# FingersFlexpcb.net
KiCad netlist of a schematic drawn in EAGLE
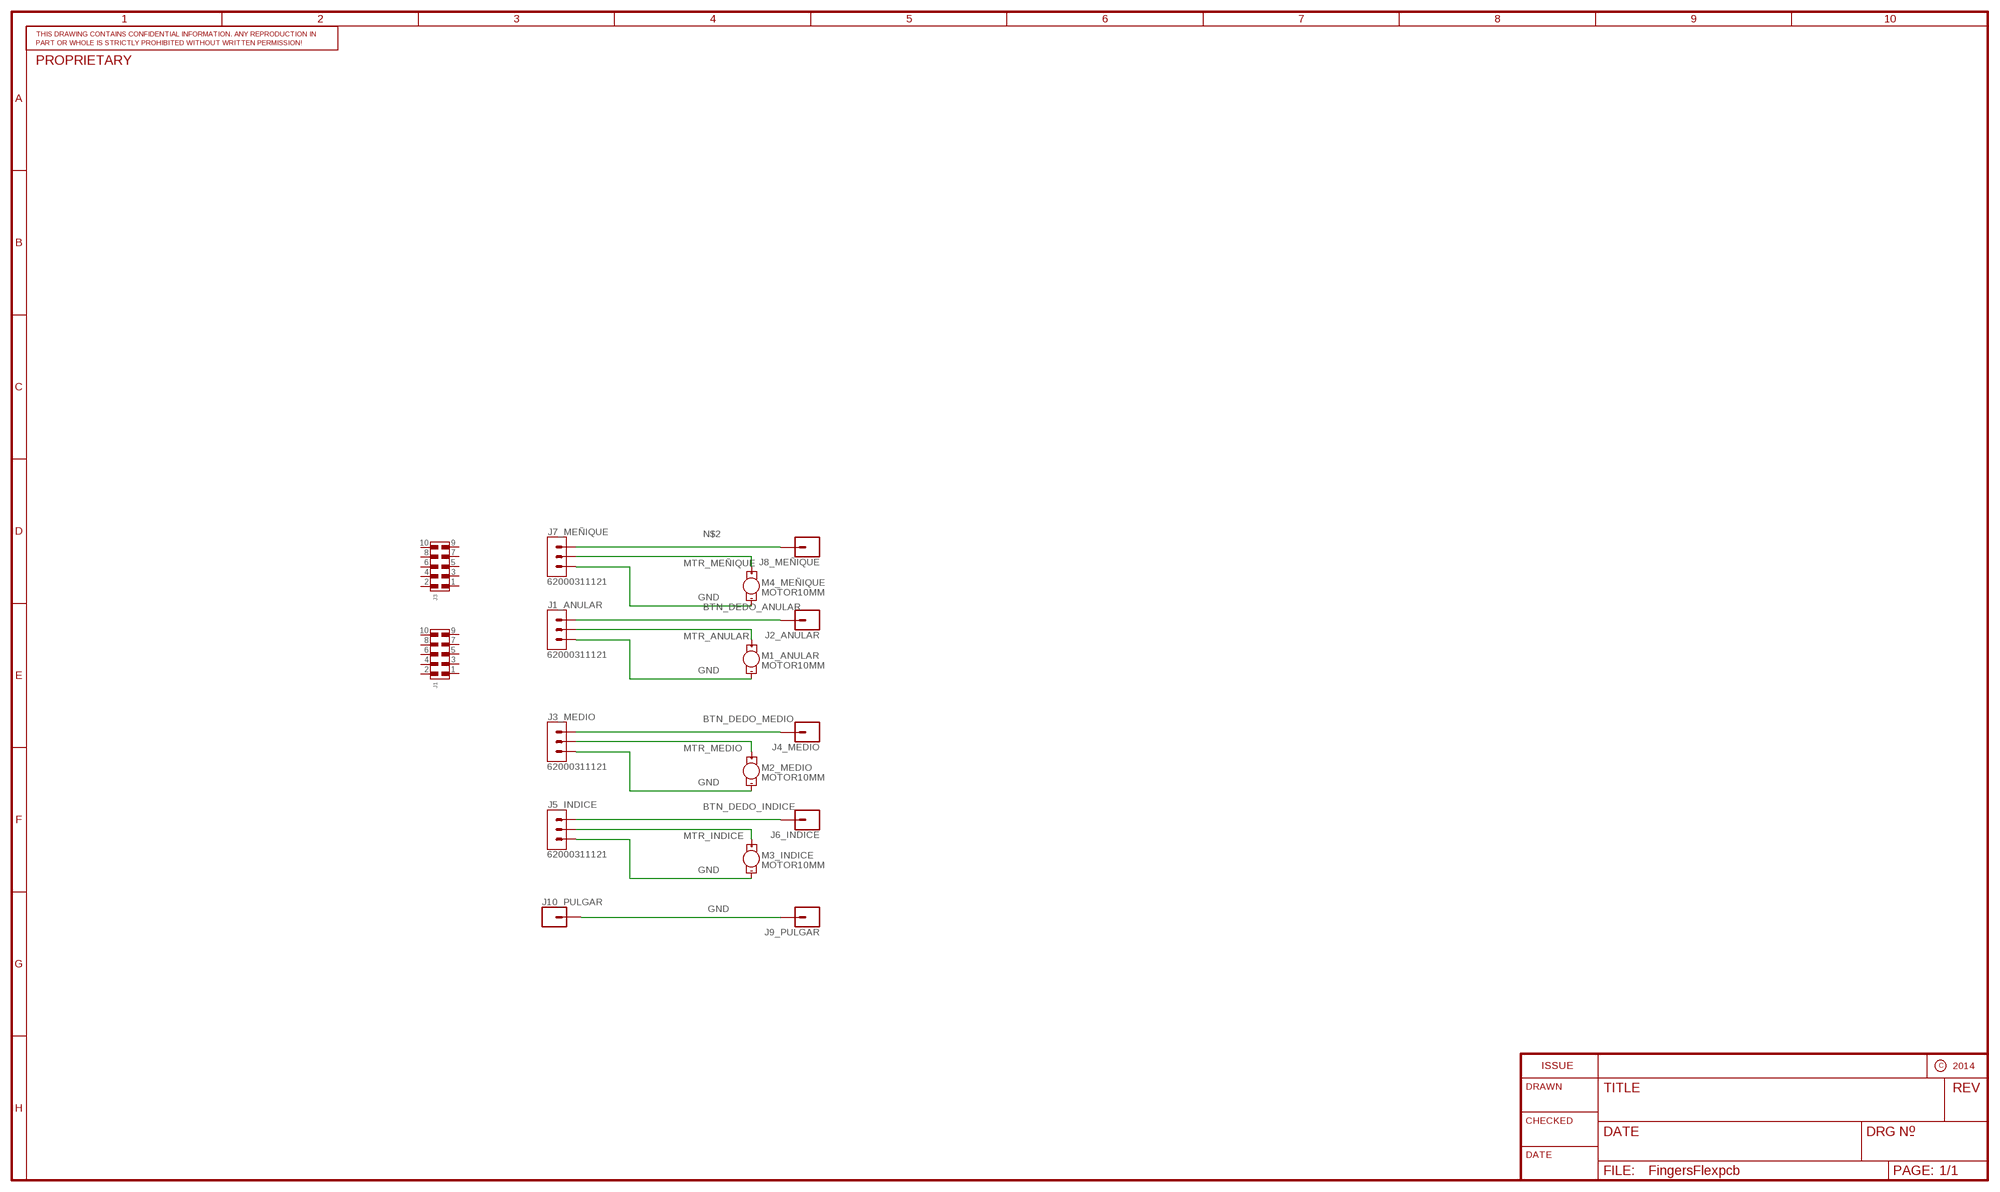
[diagram p0: schematic, sheet 1]

(export (version "E")
  (design (tool "Eeschema 10.0.6"))
  (components
    (comp (ref "J1")
      (value "6100XX21121_61001021121")
      (footprint "eagle-import:61001021121")
      (libsource (lib "eagle-import") (part "6100XX21121_61001021121"))
    )
    (comp (ref "J1_ANULAR")
      (value "62000311121")
      (footprint "eagle-import:62000311121")
      (fields (field (name "MANUFACTURER") " Würth Elektronik ") (field (name "CREATED_BY") "PCBLayout.com"))
      (libsource (lib "eagle-import") (part "62000311121"))
    )
    (comp (ref "J2_ANULAR")
      (value "CONN_01")
      (footprint "eagle-import:1X01")
      (libsource (lib "eagle-import") (part "CONN_01"))
    )
    (comp (ref "J3")
      (value "6100XX21121_61001021121")
      (footprint "eagle-import:61001021121")
      (libsource (lib "eagle-import") (part "6100XX21121_61001021121"))
    )
    (comp (ref "J3_MEDIO")
      (value "62000311121")
      (footprint "eagle-import:62000311121")
      (fields (field (name "MANUFACTURER") " Würth Elektronik ") (field (name "CREATED_BY") "PCBLayout.com"))
      (libsource (lib "eagle-import") (part "62000311121"))
    )
    (comp (ref "J4_MEDIO")
      (value "CONN_01")
      (footprint "eagle-import:1X01")
      (libsource (lib "eagle-import") (part "CONN_01"))
    )
    (comp (ref "J5_INDICE")
      (value "62000311121")
      (footprint "eagle-import:62000311121")
      (fields (field (name "MANUFACTURER") " Würth Elektronik ") (field (name "CREATED_BY") "PCBLayout.com"))
      (libsource (lib "eagle-import") (part "62000311121"))
    )
    (comp (ref "J6_INDICE")
      (value "CONN_01")
      (footprint "eagle-import:1X01")
      (libsource (lib "eagle-import") (part "CONN_01"))
    )
    (comp (ref "J7_MEÑIQUE")
      (value "62000311121")
      (footprint "eagle-import:62000311121")
      (fields (field (name "MANUFACTURER") " Würth Elektronik ") (field (name "CREATED_BY") "PCBLayout.com"))
      (libsource (lib "eagle-import") (part "62000311121"))
    )
    (comp (ref "J8_MEÑIQUE")
      (value "CONN_01")
      (footprint "eagle-import:1X01")
      (libsource (lib "eagle-import") (part "CONN_01"))
    )
    (comp (ref "J9_PULGAR")
      (value "CONN_01")
      (footprint "eagle-import:1X01")
      (libsource (lib "eagle-import") (part "CONN_01"))
    )
    (comp (ref "J10_PULGAR")
      (value "CONN_01")
      (footprint "eagle-import:1X01")
      (libsource (lib "eagle-import") (part "CONN_01"))
    )
    (comp (ref "M1_ANULAR")
      (value "MOTOR10MM")
      (footprint "eagle-import:VIBE-MOTOR-10MM")
      (libsource (lib "eagle-import") (part "MOTOR10MM"))
    )
    (comp (ref "M2_MEDIO")
      (value "MOTOR10MM")
      (footprint "eagle-import:VIBE-MOTOR-10MM")
      (libsource (lib "eagle-import") (part "MOTOR10MM"))
    )
    (comp (ref "M3_INDICE")
      (value "MOTOR10MM")
      (footprint "eagle-import:VIBE-MOTOR-10MM")
      (libsource (lib "eagle-import") (part "MOTOR10MM"))
    )
    (comp (ref "M4_MEÑIQUE")
      (value "MOTOR10MM")
      (footprint "eagle-import:VIBE-MOTOR-10MM")
      (libsource (lib "eagle-import") (part "MOTOR10MM"))
    )
  )
  (nets
    (net (code "1") (name "/BTN_DEDO_ANULAR") (class "Default")
      (node (ref "J1_ANULAR") (pin "1") (pinfunction "1_1") (pintype "passive"))
      (node (ref "J2_ANULAR") (pin "1") (pinfunction "1_1") (pintype "passive"))
    )
    (net (code "2") (name "/BTN_DEDO_INDICE") (class "Default")
      (node (ref "J5_INDICE") (pin "1") (pinfunction "1_1") (pintype "passive"))
      (node (ref "J6_INDICE") (pin "1") (pinfunction "1_1") (pintype "passive"))
    )
    (net (code "3") (name "/BTN_DEDO_MEDIO") (class "Default")
      (node (ref "J3_MEDIO") (pin "1") (pinfunction "1_1") (pintype "passive"))
      (node (ref "J4_MEDIO") (pin "1") (pinfunction "1_1") (pintype "passive"))
    )
    (net (code "4") (name "/GND") (class "Default")
      (node (ref "J10_PULGAR") (pin "1") (pinfunction "1_1") (pintype "passive"))
      (node (ref "J1_ANULAR") (pin "3") (pinfunction "3_3") (pintype "passive"))
      (node (ref "J3_MEDIO") (pin "3") (pinfunction "3_3") (pintype "passive"))
      (node (ref "J5_INDICE") (pin "3") (pinfunction "3_3") (pintype "passive"))
      (node (ref "J7_MEÑIQUE") (pin "3") (pinfunction "3_3") (pintype "passive"))
      (node (ref "J9_PULGAR") (pin "1") (pinfunction "1_1") (pintype "passive"))
      (node (ref "M1_ANULAR") (pin "-") (pinfunction "-_-") (pintype "bidirectional"))
      (node (ref "M2_MEDIO") (pin "-") (pinfunction "-_-") (pintype "bidirectional"))
      (node (ref "M3_INDICE") (pin "-") (pinfunction "-_-") (pintype "bidirectional"))
      (node (ref "M4_MEÑIQUE") (pin "-") (pinfunction "-_-") (pintype "bidirectional"))
    )
    (net (code "5") (name "/MTR_ANULAR") (class "Default")
      (node (ref "J1_ANULAR") (pin "2") (pinfunction "2_2") (pintype "passive"))
      (node (ref "M1_ANULAR") (pin "+") (pinfunction "+_+") (pintype "bidirectional"))
    )
    (net (code "6") (name "/MTR_INDICE") (class "Default")
      (node (ref "J5_INDICE") (pin "2") (pinfunction "2_2") (pintype "passive"))
      (node (ref "M3_INDICE") (pin "+") (pinfunction "+_+") (pintype "bidirectional"))
    )
    (net (code "7") (name "/MTR_MEDIO") (class "Default")
      (node (ref "J3_MEDIO") (pin "2") (pinfunction "2_2") (pintype "passive"))
      (node (ref "M2_MEDIO") (pin "+") (pinfunction "+_+") (pintype "bidirectional"))
    )
    (net (code "8") (name "/MTR_MEÑIQUE") (class "Default")
      (node (ref "J7_MEÑIQUE") (pin "2") (pinfunction "2_2") (pintype "passive"))
      (node (ref "M4_MEÑIQUE") (pin "+") (pinfunction "+_+") (pintype "bidirectional"))
    )
    (net (code "9") (name "/N$2") (class "Default")
      (node (ref "J7_MEÑIQUE") (pin "1") (pinfunction "1_1") (pintype "passive"))
      (node (ref "J8_MEÑIQUE") (pin "1") (pinfunction "1_1") (pintype "passive"))
    )
    (net (code "10") (name "unconnected-(J1-Pad1)") (class "Default")
      (node (ref "J1") (pin "1") (pinfunction "1_1") (pintype "passive"))
    )
    (net (code "11") (name "unconnected-(J1-Pad2)") (class "Default")
      (node (ref "J1") (pin "2") (pinfunction "2_2") (pintype "passive"))
    )
    (net (code "12") (name "unconnected-(J1-Pad3)") (class "Default")
      (node (ref "J1") (pin "3") (pinfunction "3_3") (pintype "passive"))
    )
    (net (code "13") (name "unconnected-(J1-Pad4)") (class "Default")
      (node (ref "J1") (pin "4") (pinfunction "4_4") (pintype "passive"))
    )
    (net (code "14") (name "unconnected-(J1-Pad5)") (class "Default")
      (node (ref "J1") (pin "5") (pinfunction "5_5") (pintype "passive"))
    )
    (net (code "15") (name "unconnected-(J1-Pad6)") (class "Default")
      (node (ref "J1") (pin "6") (pinfunction "6_6") (pintype "passive"))
    )
    (net (code "16") (name "unconnected-(J1-Pad7)") (class "Default")
      (node (ref "J1") (pin "7") (pinfunction "7_7") (pintype "passive"))
    )
    (net (code "17") (name "unconnected-(J1-Pad8)") (class "Default")
      (node (ref "J1") (pin "8") (pinfunction "8_8") (pintype "passive"))
    )
    (net (code "18") (name "unconnected-(J1-Pad9)") (class "Default")
      (node (ref "J1") (pin "9") (pinfunction "9_9") (pintype "passive"))
    )
    (net (code "19") (name "unconnected-(J1-Pad10)") (class "Default")
      (node (ref "J1") (pin "10") (pinfunction "10_10") (pintype "passive"))
    )
    (net (code "20") (name "unconnected-(J3-Pad1)") (class "Default")
      (node (ref "J3") (pin "1") (pinfunction "1_1") (pintype "passive"))
    )
    (net (code "21") (name "unconnected-(J3-Pad2)") (class "Default")
      (node (ref "J3") (pin "2") (pinfunction "2_2") (pintype "passive"))
    )
    (net (code "22") (name "unconnected-(J3-Pad3)") (class "Default")
      (node (ref "J3") (pin "3") (pinfunction "3_3") (pintype "passive"))
    )
    (net (code "23") (name "unconnected-(J3-Pad4)") (class "Default")
      (node (ref "J3") (pin "4") (pinfunction "4_4") (pintype "passive"))
    )
    (net (code "24") (name "unconnected-(J3-Pad5)") (class "Default")
      (node (ref "J3") (pin "5") (pinfunction "5_5") (pintype "passive"))
    )
    (net (code "25") (name "unconnected-(J3-Pad6)") (class "Default")
      (node (ref "J3") (pin "6") (pinfunction "6_6") (pintype "passive"))
    )
    (net (code "26") (name "unconnected-(J3-Pad7)") (class "Default")
      (node (ref "J3") (pin "7") (pinfunction "7_7") (pintype "passive"))
    )
    (net (code "27") (name "unconnected-(J3-Pad8)") (class "Default")
      (node (ref "J3") (pin "8") (pinfunction "8_8") (pintype "passive"))
    )
    (net (code "28") (name "unconnected-(J3-Pad9)") (class "Default")
      (node (ref "J3") (pin "9") (pinfunction "9_9") (pintype "passive"))
    )
    (net (code "29") (name "unconnected-(J3-Pad10)") (class "Default")
      (node (ref "J3") (pin "10") (pinfunction "10_10") (pintype "passive"))
    )
  )
)
